# onion_dip_v2.net
KiCad netlist of a schematic drawn in EAGLE
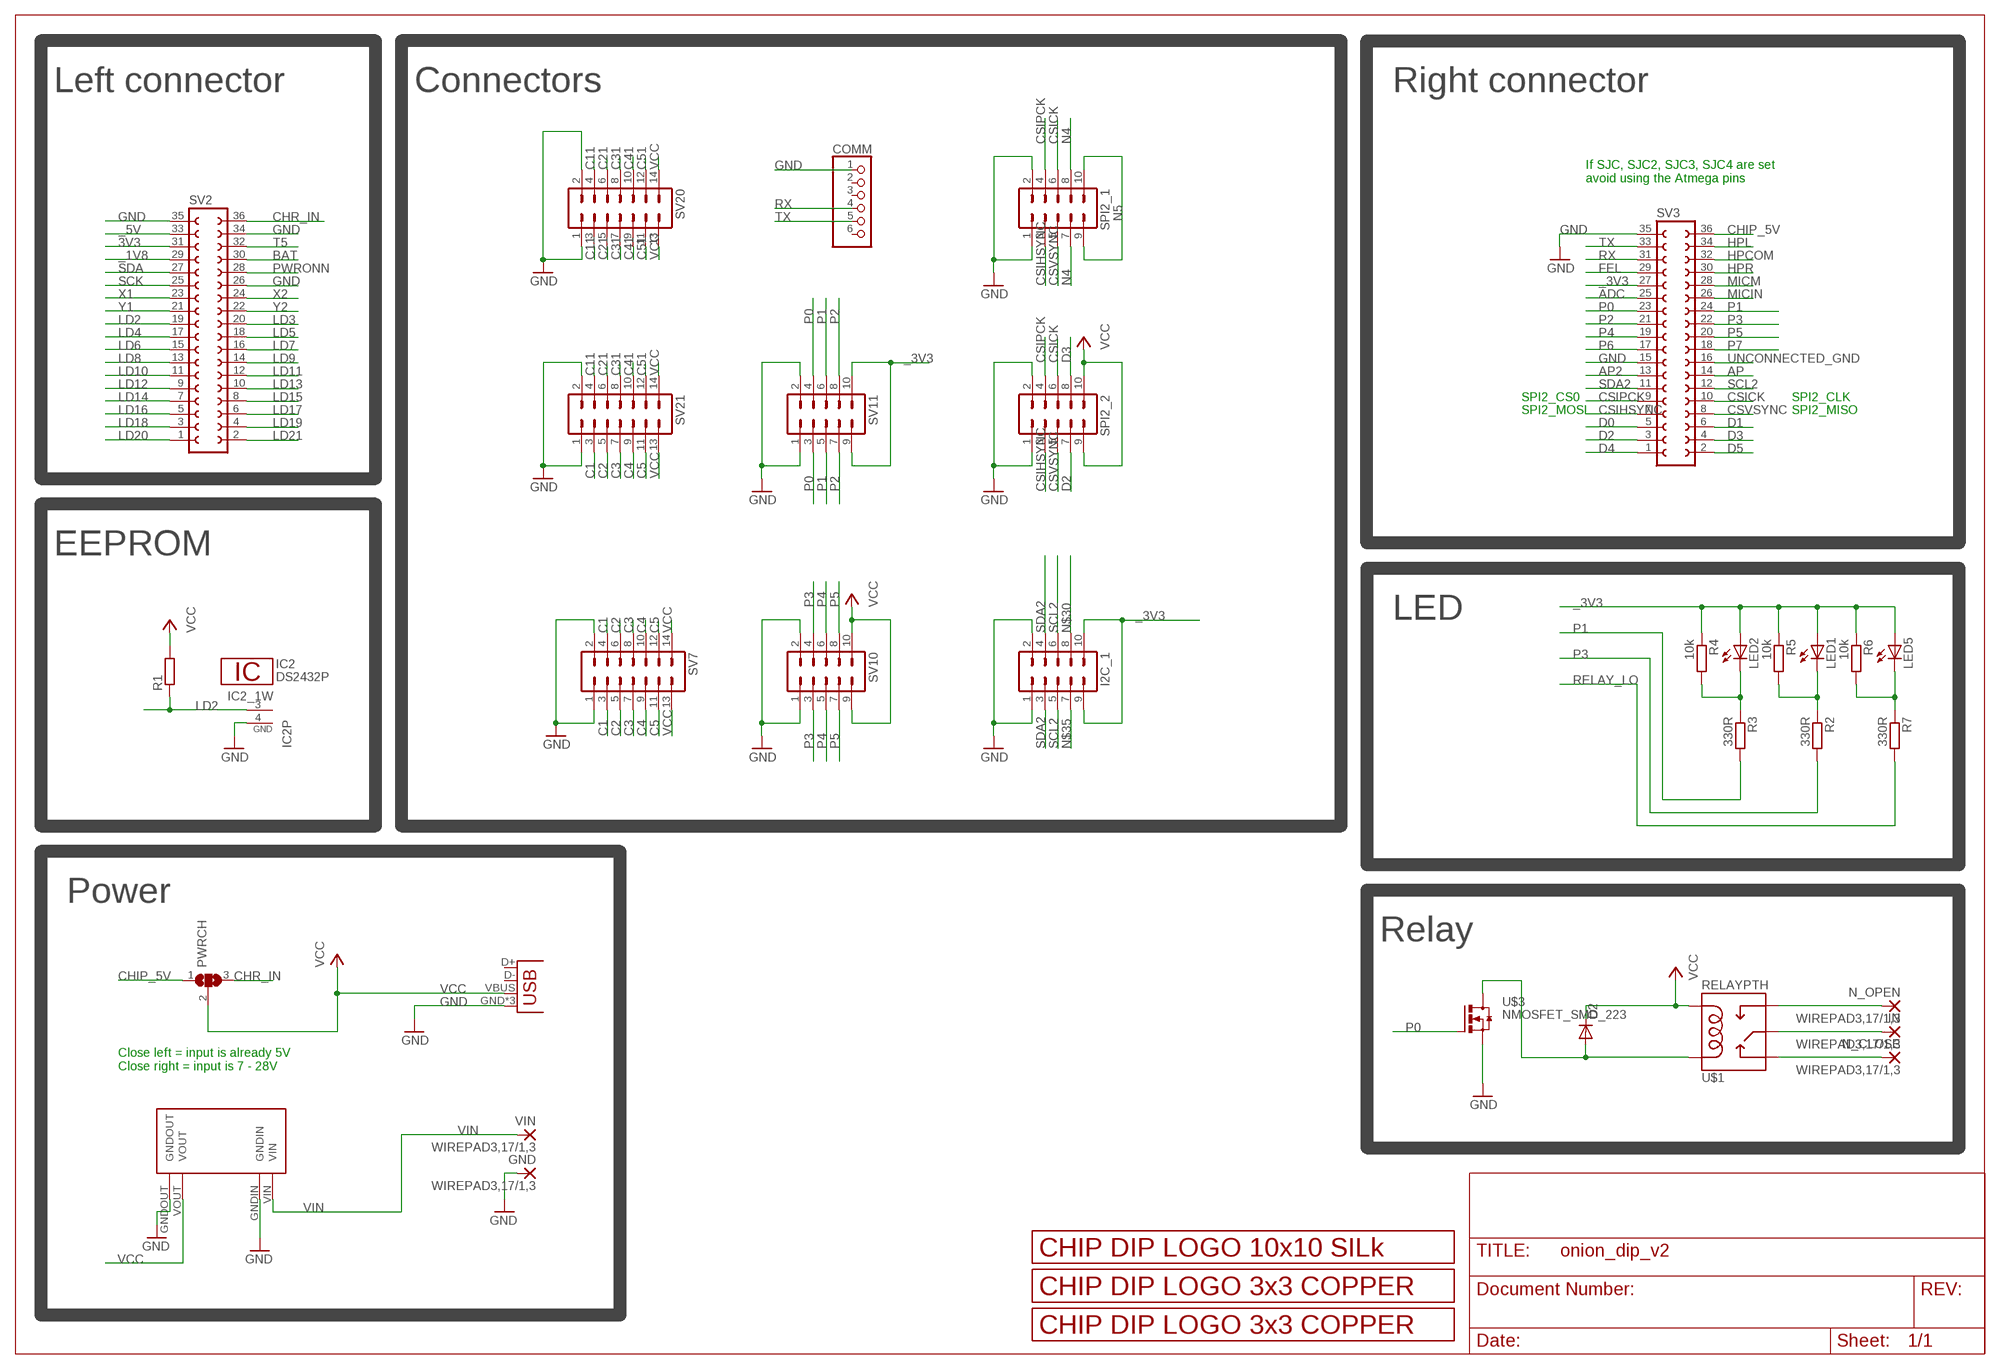
[diagram p0: schematic, sheet 1]

(export (version "E")
  (design (tool "Eeschema 10.0.6"))
  (components
    (comp (ref "COMM")
      (value "PINHD-1X6")
      (footprint "eagle-import:1X06")
      (libsource (lib "eagle-import") (part "PINHD-1X6"))
    )
    (comp (ref "D2")
      (value "DIODE-SMB")
      (footprint "eagle-import:SMB")
      (libsource (lib "eagle-import") (part "DIODE-SMB"))
    )
    (comp (ref "GND")
      (value "WIREPAD3,17/1,3")
      (footprint "eagle-import:3,17_1,3")
      (libsource (lib "eagle-import") (part "WIREPAD3,17/1,3"))
    )
    (comp (ref "I2C_1")
      (value "MA05-2")
      (footprint "eagle-import:MA05-2")
      (libsource (lib "eagle-import") (part "MA05-2"))
    )
    (comp (ref "IC2")
      (value "DS2432P")
      (footprint "eagle-import:TSOC6")
      (libsource (lib "eagle-import") (part "DS2432P"))
    )
    (comp (ref "IN")
      (value "WIREPAD3,17/1,3")
      (footprint "eagle-import:3,17_1,3")
      (libsource (lib "eagle-import") (part "WIREPAD3,17/1,3"))
    )
    (comp (ref "LED1")
      (value "LEDCHIP-LED0805")
      (footprint "eagle-import:CHIP-LED0805")
      (libsource (lib "eagle-import") (part "LEDCHIP-LED0805"))
    )
    (comp (ref "LED2")
      (value "LEDCHIP-LED0805")
      (footprint "eagle-import:CHIP-LED0805")
      (libsource (lib "eagle-import") (part "LEDCHIP-LED0805"))
    )
    (comp (ref "LED5")
      (value "LEDCHIP-LED0805")
      (footprint "eagle-import:CHIP-LED0805")
      (libsource (lib "eagle-import") (part "LEDCHIP-LED0805"))
    )
    (comp (ref "N_CLOSE")
      (value "WIREPAD3,17/1,3")
      (footprint "eagle-import:3,17_1,3")
      (libsource (lib "eagle-import") (part "WIREPAD3,17/1,3"))
    )
    (comp (ref "N_OPEN")
      (value "WIREPAD3,17/1,3")
      (footprint "eagle-import:3,17_1,3")
      (libsource (lib "eagle-import") (part "WIREPAD3,17/1,3"))
    )
    (comp (ref "PWRCH")
      (value "SJ2W")
      (footprint "eagle-import:SJ_2")
      (libsource (lib "eagle-import") (part "SJ2W"))
    )
    (comp (ref "R1")
      (value "R-EU_R0805")
      (footprint "eagle-import:R0805")
      (libsource (lib "eagle-import") (part "R-EU_R0805"))
    )
    (comp (ref "R2")
      (value "330R")
      (footprint "eagle-import:R0805")
      (libsource (lib "eagle-import") (part "R-EU_R0805"))
    )
    (comp (ref "R3")
      (value "330R")
      (footprint "eagle-import:R0805")
      (libsource (lib "eagle-import") (part "R-EU_R0805"))
    )
    (comp (ref "R4")
      (value "10k")
      (footprint "eagle-import:R0805")
      (libsource (lib "eagle-import") (part "R-EU_R0805"))
    )
    (comp (ref "R5")
      (value "10k")
      (footprint "eagle-import:R0805")
      (libsource (lib "eagle-import") (part "R-EU_R0805"))
    )
    (comp (ref "R6")
      (value "10k")
      (footprint "eagle-import:R0805")
      (libsource (lib "eagle-import") (part "R-EU_R0805"))
    )
    (comp (ref "R7")
      (value "330R")
      (footprint "eagle-import:R0805")
      (libsource (lib "eagle-import") (part "R-EU_R0805"))
    )
    (comp (ref "SPI2_1")
      (value "MA05-2")
      (footprint "eagle-import:MA05-2")
      (libsource (lib "eagle-import") (part "MA05-2"))
    )
    (comp (ref "SPI2_2")
      (value "MA05-2")
      (footprint "eagle-import:MA05-2")
      (libsource (lib "eagle-import") (part "MA05-2"))
    )
    (comp (ref "SV2")
      (value "FE18-2")
      (footprint "eagle-import:FE18-2")
      (libsource (lib "eagle-import") (part "FE18-2"))
    )
    (comp (ref "SV3")
      (value "FE18-2")
      (footprint "eagle-import:FE18-2")
      (libsource (lib "eagle-import") (part "FE18-2"))
    )
    (comp (ref "SV7")
      (value "MA07-2")
      (footprint "eagle-import:MA07-2")
      (libsource (lib "eagle-import") (part "MA07-2"))
    )
    (comp (ref "SV10")
      (value "MA05-2")
      (footprint "eagle-import:MA05-2")
      (libsource (lib "eagle-import") (part "MA05-2"))
    )
    (comp (ref "SV11")
      (value "MA05-2")
      (footprint "eagle-import:MA05-2")
      (libsource (lib "eagle-import") (part "MA05-2"))
    )
    (comp (ref "SV20")
      (value "MA07-2")
      (footprint "eagle-import:MA07-2")
      (libsource (lib "eagle-import") (part "MA07-2"))
    )
    (comp (ref "SV21")
      (value "MA07-2")
      (footprint "eagle-import:MA07-2")
      (libsource (lib "eagle-import") (part "MA07-2"))
    )
    (comp (ref "U$1")
      (value "RELAYPTH")
      (footprint "eagle-import:SRD-05VDC-SL-C")
      (libsource (lib "eagle-import") (part "RELAYPTH"))
    )
    (comp (ref "U$3")
      (value "NMOSFET_SMD_223")
      (footprint "eagle-import:SOT223")
      (libsource (lib "eagle-import") (part "NMOSFET_SMD_223"))
    )
    (comp (ref "U$4")
      (value "LOGO_3X3_COPPER")
      (footprint "eagle-import:LOGO_3X3_COPPER")
      (libsource (lib "eagle-import") (part "LOGO_3X3_COPPER"))
    )
    (comp (ref "U$5")
      (value "LOGO_10X10_SILK")
      (footprint "eagle-import:LOGO_10X10_SILK")
      (libsource (lib "eagle-import") (part "LOGO_10X10_SILK"))
    )
    (comp (ref "U$6")
      (value "LOGO_3X3_COPPER")
      (footprint "eagle-import:LOGO_3X3_COPPER")
      (libsource (lib "eagle-import") (part "LOGO_3X3_COPPER"))
    )
    (comp (ref "U$9")
      (value "MP1584EN_FRAMELESS")
      (footprint "eagle-import:MP1584EN_FRAMELESS")
      (libsource (lib "eagle-import") (part "MP1584EN_FRAMELESS"))
    )
    (comp (ref "USB")
      (value "USBUSB-MICROB-SMT-DIP")
      (footprint "eagle-import:USB-MICROB-SMT-DIP")
      (libsource (lib "eagle-import") (part "USBUSB-MICROB-SMT-DIP"))
    )
    (comp (ref "VIN")
      (value "WIREPAD3,17/1,3")
      (footprint "eagle-import:3,17_1,3")
      (libsource (lib "eagle-import") (part "WIREPAD3,17/1,3"))
    )
  )
  (nets
    (net (code "1") (name "/3V3") (class "Default")
      (node (ref "SV2") (pin "31") (pinfunction "31_31") (pintype "passive"))
    )
    (net (code "2") (name "/ADC") (class "Default")
      (node (ref "SV3") (pin "25") (pinfunction "25_25") (pintype "passive"))
    )
    (net (code "3") (name "/AP") (class "Default")
      (node (ref "SV3") (pin "14") (pinfunction "14_14") (pintype "passive"))
    )
    (net (code "4") (name "/AP2") (class "Default")
      (node (ref "SV3") (pin "13") (pinfunction "13_13") (pintype "passive"))
    )
    (net (code "5") (name "/BAT") (class "Default")
      (node (ref "SV2") (pin "30") (pinfunction "30_30") (pintype "passive"))
    )
    (net (code "6") (name "/C1") (class "Default")
      (node (ref "SV21") (pin "3") (pinfunction "3_3") (pintype "passive"))
      (node (ref "SV7") (pin "3") (pinfunction "3_3") (pintype "passive"))
      (node (ref "SV7") (pin "4") (pinfunction "4_4") (pintype "passive"))
    )
    (net (code "7") (name "/C2") (class "Default")
      (node (ref "SV21") (pin "5") (pinfunction "5_5") (pintype "passive"))
      (node (ref "SV7") (pin "5") (pinfunction "5_5") (pintype "passive"))
      (node (ref "SV7") (pin "6") (pinfunction "6_6") (pintype "passive"))
    )
    (net (code "8") (name "/C3") (class "Default")
      (node (ref "SV21") (pin "7") (pinfunction "7_7") (pintype "passive"))
      (node (ref "SV7") (pin "7") (pinfunction "7_7") (pintype "passive"))
      (node (ref "SV7") (pin "8") (pinfunction "8_8") (pintype "passive"))
    )
    (net (code "9") (name "/C4") (class "Default")
      (node (ref "SV21") (pin "9") (pinfunction "9_9") (pintype "passive"))
      (node (ref "SV7") (pin "10") (pinfunction "10_10") (pintype "passive"))
      (node (ref "SV7") (pin "9") (pinfunction "9_9") (pintype "passive"))
    )
    (net (code "10") (name "/C5") (class "Default")
      (node (ref "SV21") (pin "11") (pinfunction "11_11") (pintype "passive"))
      (node (ref "SV7") (pin "11") (pinfunction "11_11") (pintype "passive"))
      (node (ref "SV7") (pin "12") (pinfunction "12_12") (pintype "passive"))
    )
    (net (code "11") (name "/C11") (class "Default")
      (node (ref "SV20") (pin "3") (pinfunction "3_3") (pintype "passive"))
      (node (ref "SV20") (pin "4") (pinfunction "4_4") (pintype "passive"))
      (node (ref "SV21") (pin "4") (pinfunction "4_4") (pintype "passive"))
    )
    (net (code "12") (name "/C21") (class "Default")
      (node (ref "SV20") (pin "5") (pinfunction "5_5") (pintype "passive"))
      (node (ref "SV20") (pin "6") (pinfunction "6_6") (pintype "passive"))
      (node (ref "SV21") (pin "6") (pinfunction "6_6") (pintype "passive"))
    )
    (net (code "13") (name "/C31") (class "Default")
      (node (ref "SV20") (pin "7") (pinfunction "7_7") (pintype "passive"))
      (node (ref "SV20") (pin "8") (pinfunction "8_8") (pintype "passive"))
      (node (ref "SV21") (pin "8") (pinfunction "8_8") (pintype "passive"))
    )
    (net (code "14") (name "/C41") (class "Default")
      (node (ref "SV20") (pin "10") (pinfunction "10_10") (pintype "passive"))
      (node (ref "SV20") (pin "9") (pinfunction "9_9") (pintype "passive"))
      (node (ref "SV21") (pin "10") (pinfunction "10_10") (pintype "passive"))
    )
    (net (code "15") (name "/C51") (class "Default")
      (node (ref "SV20") (pin "11") (pinfunction "11_11") (pintype "passive"))
      (node (ref "SV20") (pin "12") (pinfunction "12_12") (pintype "passive"))
      (node (ref "SV21") (pin "12") (pinfunction "12_12") (pintype "passive"))
    )
    (net (code "16") (name "/CHIP_5V") (class "Default")
      (node (ref "PWRCH") (pin "1") (pinfunction "1_1") (pintype "passive"))
      (node (ref "SV3") (pin "36") (pinfunction "36_36") (pintype "passive"))
    )
    (net (code "17") (name "/CHR_IN") (class "Default")
      (node (ref "PWRCH") (pin "3") (pinfunction "3_3") (pintype "passive"))
      (node (ref "SV2") (pin "36") (pinfunction "36_36") (pintype "passive"))
    )
    (net (code "18") (name "/CSICK") (class "Default")
      (node (ref "SPI2_1") (pin "6") (pinfunction "6_6") (pintype "passive"))
      (node (ref "SPI2_2") (pin "6") (pinfunction "6_6") (pintype "passive"))
      (node (ref "SV3") (pin "10") (pinfunction "10_10") (pintype "passive"))
    )
    (net (code "19") (name "/CSIHSYNC") (class "Default")
      (node (ref "SPI2_1") (pin "3") (pinfunction "3_3") (pintype "passive"))
      (node (ref "SPI2_2") (pin "3") (pinfunction "3_3") (pintype "passive"))
      (node (ref "SV3") (pin "7") (pinfunction "7_7") (pintype "passive"))
    )
    (net (code "20") (name "/CSIPCK") (class "Default")
      (node (ref "SPI2_1") (pin "4") (pinfunction "4_4") (pintype "passive"))
      (node (ref "SPI2_2") (pin "4") (pinfunction "4_4") (pintype "passive"))
      (node (ref "SV3") (pin "9") (pinfunction "9_9") (pintype "passive"))
    )
    (net (code "21") (name "/CSVSYNC") (class "Default")
      (node (ref "SPI2_1") (pin "5") (pinfunction "5_5") (pintype "passive"))
      (node (ref "SPI2_2") (pin "5") (pinfunction "5_5") (pintype "passive"))
      (node (ref "SV3") (pin "8") (pinfunction "8_8") (pintype "passive"))
    )
    (net (code "22") (name "/D0") (class "Default")
      (node (ref "SV3") (pin "5") (pinfunction "5_5") (pintype "passive"))
    )
    (net (code "23") (name "/D1") (class "Default")
      (node (ref "SV3") (pin "6") (pinfunction "6_6") (pintype "passive"))
    )
    (net (code "24") (name "/D2") (class "Default")
      (node (ref "SPI2_2") (pin "7") (pinfunction "7_7") (pintype "passive"))
      (node (ref "SV3") (pin "3") (pinfunction "3_3") (pintype "passive"))
    )
    (net (code "25") (name "/D3") (class "Default")
      (node (ref "SPI2_2") (pin "8") (pinfunction "8_8") (pintype "passive"))
      (node (ref "SV3") (pin "4") (pinfunction "4_4") (pintype "passive"))
    )
    (net (code "26") (name "/D4") (class "Default")
      (node (ref "SV3") (pin "1") (pinfunction "1_1") (pintype "passive"))
    )
    (net (code "27") (name "/D5") (class "Default")
      (node (ref "SV3") (pin "2") (pinfunction "2_2") (pintype "passive"))
    )
    (net (code "28") (name "/FEL") (class "Default")
      (node (ref "SV3") (pin "29") (pinfunction "29_29") (pintype "passive"))
    )
    (net (code "29") (name "/HPCOM") (class "Default")
      (node (ref "SV3") (pin "32") (pinfunction "32_32") (pintype "passive"))
    )
    (net (code "30") (name "/HPL") (class "Default")
      (node (ref "SV3") (pin "34") (pinfunction "34_34") (pintype "passive"))
    )
    (net (code "31") (name "/HPR") (class "Default")
      (node (ref "SV3") (pin "30") (pinfunction "30_30") (pintype "passive"))
    )
    (net (code "32") (name "/LD2") (class "Default")
      (node (ref "IC2") (pin "3") (pinfunction "1W_3") (pintype "power_in"))
      (node (ref "R1") (pin "1") (pinfunction "1_1") (pintype "passive"))
      (node (ref "SV2") (pin "19") (pinfunction "19_19") (pintype "passive"))
    )
    (net (code "33") (name "/LD3") (class "Default")
      (node (ref "SV2") (pin "20") (pinfunction "20_20") (pintype "passive"))
    )
    (net (code "34") (name "/LD4") (class "Default")
      (node (ref "SV2") (pin "17") (pinfunction "17_17") (pintype "passive"))
    )
    (net (code "35") (name "/LD5") (class "Default")
      (node (ref "SV2") (pin "18") (pinfunction "18_18") (pintype "passive"))
    )
    (net (code "36") (name "/LD6") (class "Default")
      (node (ref "SV2") (pin "15") (pinfunction "15_15") (pintype "passive"))
    )
    (net (code "37") (name "/LD7") (class "Default")
      (node (ref "SV2") (pin "16") (pinfunction "16_16") (pintype "passive"))
    )
    (net (code "38") (name "/LD8") (class "Default")
      (node (ref "SV2") (pin "13") (pinfunction "13_13") (pintype "passive"))
    )
    (net (code "39") (name "/LD9") (class "Default")
      (node (ref "SV2") (pin "14") (pinfunction "14_14") (pintype "passive"))
    )
    (net (code "40") (name "/LD10") (class "Default")
      (node (ref "SV2") (pin "11") (pinfunction "11_11") (pintype "passive"))
    )
    (net (code "41") (name "/LD11") (class "Default")
      (node (ref "SV2") (pin "12") (pinfunction "12_12") (pintype "passive"))
    )
    (net (code "42") (name "/LD12") (class "Default")
      (node (ref "SV2") (pin "9") (pinfunction "9_9") (pintype "passive"))
    )
    (net (code "43") (name "/LD13") (class "Default")
      (node (ref "SV2") (pin "10") (pinfunction "10_10") (pintype "passive"))
    )
    (net (code "44") (name "/LD14") (class "Default")
      (node (ref "SV2") (pin "7") (pinfunction "7_7") (pintype "passive"))
    )
    (net (code "45") (name "/LD15") (class "Default")
      (node (ref "SV2") (pin "8") (pinfunction "8_8") (pintype "passive"))
    )
    (net (code "46") (name "/LD16") (class "Default")
      (node (ref "SV2") (pin "5") (pinfunction "5_5") (pintype "passive"))
    )
    (net (code "47") (name "/LD17") (class "Default")
      (node (ref "SV2") (pin "6") (pinfunction "6_6") (pintype "passive"))
    )
    (net (code "48") (name "/LD18") (class "Default")
      (node (ref "SV2") (pin "3") (pinfunction "3_3") (pintype "passive"))
    )
    (net (code "49") (name "/LD19") (class "Default")
      (node (ref "SV2") (pin "4") (pinfunction "4_4") (pintype "passive"))
    )
    (net (code "50") (name "/LD20") (class "Default")
      (node (ref "SV2") (pin "1") (pinfunction "1_1") (pintype "passive"))
    )
    (net (code "51") (name "/LD21") (class "Default")
      (node (ref "SV2") (pin "2") (pinfunction "2_2") (pintype "passive"))
    )
    (net (code "52") (name "/MICIN") (class "Default")
      (node (ref "SV3") (pin "26") (pinfunction "26_26") (pintype "passive"))
    )
    (net (code "53") (name "/MICM") (class "Default")
      (node (ref "SV3") (pin "28") (pinfunction "28_28") (pintype "passive"))
    )
    (net (code "54") (name "/N$30") (class "Default")
      (node (ref "I2C_1") (pin "8") (pinfunction "8_8") (pintype "passive"))
    )
    (net (code "55") (name "/N$35") (class "Default")
      (node (ref "I2C_1") (pin "7") (pinfunction "7_7") (pintype "passive"))
    )
    (net (code "56") (name "/N4") (class "Default")
      (node (ref "SPI2_1") (pin "7") (pinfunction "7_7") (pintype "passive"))
      (node (ref "SPI2_1") (pin "8") (pinfunction "8_8") (pintype "passive"))
    )
    (net (code "57") (name "/N5") (class "Default")
      (node (ref "SPI2_1") (pin "10") (pinfunction "10_10") (pintype "passive"))
      (node (ref "SPI2_1") (pin "9") (pinfunction "9_9") (pintype "passive"))
    )
    (net (code "58") (name "/P0") (class "Default")
      (node (ref "SV11") (pin "3") (pinfunction "3_3") (pintype "passive"))
      (node (ref "SV11") (pin "4") (pinfunction "4_4") (pintype "passive"))
      (node (ref "SV3") (pin "23") (pinfunction "23_23") (pintype "passive"))
      (node (ref "U$3") (pin "1") (pinfunction "G_1") (pintype "passive"))
    )
    (net (code "59") (name "/P1") (class "Default")
      (node (ref "R3") (pin "2") (pinfunction "2_2") (pintype "passive"))
      (node (ref "SV11") (pin "5") (pinfunction "5_5") (pintype "passive"))
      (node (ref "SV11") (pin "6") (pinfunction "6_6") (pintype "passive"))
      (node (ref "SV3") (pin "24") (pinfunction "24_24") (pintype "passive"))
    )
    (net (code "60") (name "/P2") (class "Default")
      (node (ref "SV11") (pin "7") (pinfunction "7_7") (pintype "passive"))
      (node (ref "SV11") (pin "8") (pinfunction "8_8") (pintype "passive"))
      (node (ref "SV3") (pin "21") (pinfunction "21_21") (pintype "passive"))
    )
    (net (code "61") (name "/P3") (class "Default")
      (node (ref "R2") (pin "2") (pinfunction "2_2") (pintype "passive"))
      (node (ref "SV10") (pin "3") (pinfunction "3_3") (pintype "passive"))
      (node (ref "SV10") (pin "4") (pinfunction "4_4") (pintype "passive"))
      (node (ref "SV3") (pin "22") (pinfunction "22_22") (pintype "passive"))
    )
    (net (code "62") (name "/P4") (class "Default")
      (node (ref "SV10") (pin "5") (pinfunction "5_5") (pintype "passive"))
      (node (ref "SV10") (pin "6") (pinfunction "6_6") (pintype "passive"))
      (node (ref "SV3") (pin "19") (pinfunction "19_19") (pintype "passive"))
    )
    (net (code "63") (name "/P5") (class "Default")
      (node (ref "SV10") (pin "7") (pinfunction "7_7") (pintype "passive"))
      (node (ref "SV10") (pin "8") (pinfunction "8_8") (pintype "passive"))
      (node (ref "SV3") (pin "20") (pinfunction "20_20") (pintype "passive"))
    )
    (net (code "64") (name "/P6") (class "Default")
      (node (ref "SV3") (pin "17") (pinfunction "17_17") (pintype "passive"))
    )
    (net (code "65") (name "/P7") (class "Default")
      (node (ref "SV3") (pin "18") (pinfunction "18_18") (pintype "passive"))
    )
    (net (code "66") (name "/PWRONN") (class "Default")
      (node (ref "SV2") (pin "28") (pinfunction "28_28") (pintype "passive"))
    )
    (net (code "67") (name "/RELAY_LO") (class "Default")
      (node (ref "D2") (pin "A") (pinfunction "A_A") (pintype "passive"))
      (node (ref "R7") (pin "2") (pinfunction "2_2") (pintype "passive"))
      (node (ref "U$1") (pin "COIL1") (pinfunction "COIL1_COIL1") (pintype "bidirectional"))
      (node (ref "U$3") (pin "2") (pinfunction "D_2") (pintype "passive"))
      (node (ref "U$3") (pin "4") (pinfunction "D_4") (pintype "passive"))
    )
    (net (code "68") (name "/RX") (class "Default")
      (node (ref "COMM") (pin "4") (pinfunction "4_4") (pintype "passive"))
      (node (ref "SV3") (pin "31") (pinfunction "31_31") (pintype "passive"))
    )
    (net (code "69") (name "/SCK") (class "Default")
      (node (ref "SV2") (pin "25") (pinfunction "25_25") (pintype "passive"))
    )
    (net (code "70") (name "/SCL2") (class "Default")
      (node (ref "I2C_1") (pin "5") (pinfunction "5_5") (pintype "passive"))
      (node (ref "I2C_1") (pin "6") (pinfunction "6_6") (pintype "passive"))
      (node (ref "SV3") (pin "12") (pinfunction "12_12") (pintype "passive"))
    )
    (net (code "71") (name "/SDA") (class "Default")
      (node (ref "SV2") (pin "27") (pinfunction "27_27") (pintype "passive"))
    )
    (net (code "72") (name "/SDA2") (class "Default")
      (node (ref "I2C_1") (pin "3") (pinfunction "3_3") (pintype "passive"))
      (node (ref "I2C_1") (pin "4") (pinfunction "4_4") (pintype "passive"))
      (node (ref "SV3") (pin "11") (pinfunction "11_11") (pintype "passive"))
    )
    (net (code "73") (name "/T5") (class "Default")
      (node (ref "SV2") (pin "32") (pinfunction "32_32") (pintype "passive"))
    )
    (net (code "74") (name "/TX") (class "Default")
      (node (ref "COMM") (pin "5") (pinfunction "5_5") (pintype "passive"))
      (node (ref "SV3") (pin "33") (pinfunction "33_33") (pintype "passive"))
    )
    (net (code "75") (name "/UNCONNECTED_GND") (class "Default")
      (node (ref "SV3") (pin "16") (pinfunction "16_16") (pintype "passive"))
    )
    (net (code "76") (name "/VIN") (class "Default")
      (node (ref "U$9") (pin "VIN") (pinfunction "VIN_VIN") (pintype "power_in"))
      (node (ref "VIN") (pin "1") (pinfunction "P_1") (pintype "passive"))
    )
    (net (code "77") (name "/X1") (class "Default")
      (node (ref "SV2") (pin "23") (pinfunction "23_23") (pintype "passive"))
    )
    (net (code "78") (name "/X2") (class "Default")
      (node (ref "SV2") (pin "24") (pinfunction "24_24") (pintype "passive"))
    )
    (net (code "79") (name "/Y1") (class "Default")
      (node (ref "SV2") (pin "21") (pinfunction "21_21") (pintype "passive"))
    )
    (net (code "80") (name "/Y2") (class "Default")
      (node (ref "SV2") (pin "22") (pinfunction "22_22") (pintype "passive"))
    )
    (net (code "81") (name "/_1V8") (class "Default")
      (node (ref "SV2") (pin "29") (pinfunction "29_29") (pintype "passive"))
    )
    (net (code "82") (name "/_3V3") (class "Default")
      (node (ref "I2C_1") (pin "10") (pinfunction "10_10") (pintype "passive"))
      (node (ref "I2C_1") (pin "9") (pinfunction "9_9") (pintype "passive"))
      (node (ref "LED1") (pin "A") (pinfunction "A_A") (pintype "passive"))
      (node (ref "LED2") (pin "A") (pinfunction "A_A") (pintype "passive"))
      (node (ref "LED5") (pin "A") (pinfunction "A_A") (pintype "passive"))
      (node (ref "R4") (pin "1") (pinfunction "1_1") (pintype "passive"))
      (node (ref "R5") (pin "1") (pinfunction "1_1") (pintype "passive"))
      (node (ref "R6") (pin "1") (pinfunction "1_1") (pintype "passive"))
      (node (ref "SV11") (pin "10") (pinfunction "10_10") (pintype "passive"))
      (node (ref "SV11") (pin "9") (pinfunction "9_9") (pintype "passive"))
      (node (ref "SV3") (pin "27") (pinfunction "27_27") (pintype "passive"))
    )
    (net (code "83") (name "/_5V") (class "Default")
      (node (ref "SV2") (pin "33") (pinfunction "33_33") (pintype "passive"))
    )
    (net (code "84") (name "GND") (class "Default")
      (node (ref "COMM") (pin "1") (pinfunction "1_1") (pintype "passive"))
      (node (ref "GND") (pin "1") (pinfunction "P_1") (pintype "passive"))
      (node (ref "I2C_1") (pin "1") (pinfunction "1_1") (pintype "passive"))
      (node (ref "I2C_1") (pin "2") (pinfunction "2_2") (pintype "passive"))
      (node (ref "IC2") (pin "4") (pinfunction "GND_4") (pintype "power_in"))
      (node (ref "SPI2_1") (pin "1") (pinfunction "1_1") (pintype "passive"))
      (node (ref "SPI2_1") (pin "2") (pinfunction "2_2") (pintype "passive"))
      (node (ref "SPI2_2") (pin "1") (pinfunction "1_1") (pintype "passive"))
      (node (ref "SPI2_2") (pin "2") (pinfunction "2_2") (pintype "passive"))
      (node (ref "SV10") (pin "1") (pinfunction "1_1") (pintype "passive"))
      (node (ref "SV10") (pin "2") (pinfunction "2_2") (pintype "passive"))
      (node (ref "SV11") (pin "1") (pinfunction "1_1") (pintype "passive"))
      (node (ref "SV11") (pin "2") (pinfunction "2_2") (pintype "passive"))
      (node (ref "SV2") (pin "26") (pinfunction "26_26") (pintype "passive"))
      (node (ref "SV2") (pin "34") (pinfunction "34_34") (pintype "passive"))
      (node (ref "SV2") (pin "35") (pinfunction "35_35") (pintype "passive"))
      (node (ref "SV20") (pin "1") (pinfunction "1_1") (pintype "passive"))
      (node (ref "SV20") (pin "2") (pinfunction "2_2") (pintype "passive"))
      (node (ref "SV21") (pin "1") (pinfunction "1_1") (pintype "passive"))
      (node (ref "SV21") (pin "2") (pinfunction "2_2") (pintype "passive"))
      (node (ref "SV3") (pin "15") (pinfunction "15_15") (pintype "passive"))
      (node (ref "SV3") (pin "35") (pinfunction "35_35") (pintype "passive"))
      (node (ref "SV7") (pin "1") (pinfunction "1_1") (pintype "passive"))
      (node (ref "SV7") (pin "2") (pinfunction "2_2") (pintype "passive"))
      (node (ref "U$3") (pin "3") (pinfunction "S_3") (pintype "passive"))
      (node (ref "U$9") (pin "GNDIN") (pinfunction "GNDIN_GNDIN") (pintype "power_in"))
      (node (ref "U$9") (pin "GNDOUT") (pinfunction "GNDOUT_GNDOUT") (pintype "power_in"))
      (node (ref "USB") (pin "GND") (pinfunction "GND_GND") (pintype "bidirectional"))
      (node (ref "USB") (pin "MT1") (pinfunction "GND_MT1") (pintype "bidirectional"))
      (node (ref "USB") (pin "MT2") (pinfunction "GND_MT2") (pintype "bidirectional"))
    )
    (net (code "85") (name "Net-(IN-P)") (class "Default")
      (node (ref "IN") (pin "1") (pinfunction "P_1") (pintype "passive"))
      (node (ref "U$1") (pin "SWCOMMON") (pinfunction "SWCOMMON_SWCOMMON") (pintype "bidirectional"))
    )
    (net (code "86") (name "Net-(LED1-PadC)") (class "Default")
      (node (ref "LED1") (pin "C") (pinfunction "C_C") (pintype "passive"))
      (node (ref "R2") (pin "1") (pinfunction "1_1") (pintype "passive"))
      (node (ref "R5") (pin "2") (pinfunction "2_2") (pintype "passive"))
    )
    (net (code "87") (name "Net-(LED2-PadC)") (class "Default")
      (node (ref "LED2") (pin "C") (pinfunction "C_C") (pintype "passive"))
      (node (ref "R3") (pin "1") (pinfunction "1_1") (pintype "passive"))
      (node (ref "R4") (pin "2") (pinfunction "2_2") (pintype "passive"))
    )
    (net (code "88") (name "Net-(LED5-PadC)") (class "Default")
      (node (ref "LED5") (pin "C") (pinfunction "C_C") (pintype "passive"))
      (node (ref "R6") (pin "2") (pinfunction "2_2") (pintype "passive"))
      (node (ref "R7") (pin "1") (pinfunction "1_1") (pintype "passive"))
    )
    (net (code "89") (name "Net-(N_CLOSE-P)") (class "Default")
      (node (ref "N_CLOSE") (pin "1") (pinfunction "P_1") (pintype "passive"))
      (node (ref "U$1") (pin "SWCLOSED") (pinfunction "SWCLOSE_SWCLOSED") (pintype "bidirectional"))
    )
    (net (code "90") (name "Net-(N_OPEN-P)") (class "Default")
      (node (ref "N_OPEN") (pin "1") (pinfunction "P_1") (pintype "passive"))
      (node (ref "U$1") (pin "SWOPEN") (pinfunction "SWOPEN_SWOPEN") (pintype "bidirectional"))
    )
    (net (code "91") (name "VCC") (class "Default")
      (node (ref "D2") (pin "C") (pinfunction "C_C") (pintype "passive"))
      (node (ref "PWRCH") (pin "2") (pinfunction "2_2") (pintype "passive"))
      (node (ref "R1") (pin "2") (pinfunction "2_2") (pintype "passive"))
      (node (ref "SPI2_2") (pin "10") (pinfunction "10_10") (pintype "passive"))
      (node (ref "SPI2_2") (pin "9") (pinfunction "9_9") (pintype "passive"))
      (node (ref "SV10") (pin "10") (pinfunction "10_10") (pintype "passive"))
      (node (ref "SV10") (pin "9") (pinfunction "9_9") (pintype "passive"))
      (node (ref "SV20") (pin "13") (pinfunction "13_13") (pintype "passive"))
      (node (ref "SV20") (pin "14") (pinfunction "14_14") (pintype "passive"))
      (node (ref "SV21") (pin "13") (pinfunction "13_13") (pintype "passive"))
      (node (ref "SV21") (pin "14") (pinfunction "14_14") (pintype "passive"))
      (node (ref "SV7") (pin "13") (pinfunction "13_13") (pintype "passive"))
      (node (ref "SV7") (pin "14") (pinfunction "14_14") (pintype "passive"))
      (node (ref "U$1") (pin "COIL0") (pinfunction "COIL0_COIL0") (pintype "bidirectional"))
      (node (ref "U$9") (pin "VOUT") (pinfunction "VOUT_VOUT") (pintype "power_in"))
      (node (ref "USB") (pin "VBUS") (pinfunction "VBUS_VBUS") (pintype "bidirectional"))
    )
    (net (code "92") (name "unconnected-(COMM-Pad2)") (class "Default")
      (node (ref "COMM") (pin "2") (pinfunction "2_2") (pintype "passive"))
    )
    (net (code "93") (name "unconnected-(COMM-Pad3)") (class "Default")
      (node (ref "COMM") (pin "3") (pinfunction "3_3") (pintype "passive"))
    )
    (net (code "94") (name "unconnected-(COMM-Pad6)") (class "Default")
      (node (ref "COMM") (pin "6") (pinfunction "6_6") (pintype "passive"))
    )
    (net (code "95") (name "unconnected-(USB-PadD+)") (class "Default")
      (node (ref "USB") (pin "D+") (pinfunction "D+_D+") (pintype "bidirectional"))
    )
    (net (code "96") (name "unconnected-(USB-PadD-)") (class "Default")
      (node (ref "USB") (pin "D-") (pinfunction "D-_D-") (pintype "bidirectional"))
    )
  )
)
